# ARE_entrenadora_modular_Arduino_mod.net
KiCad netlist of a schematic drawn in EAGLE
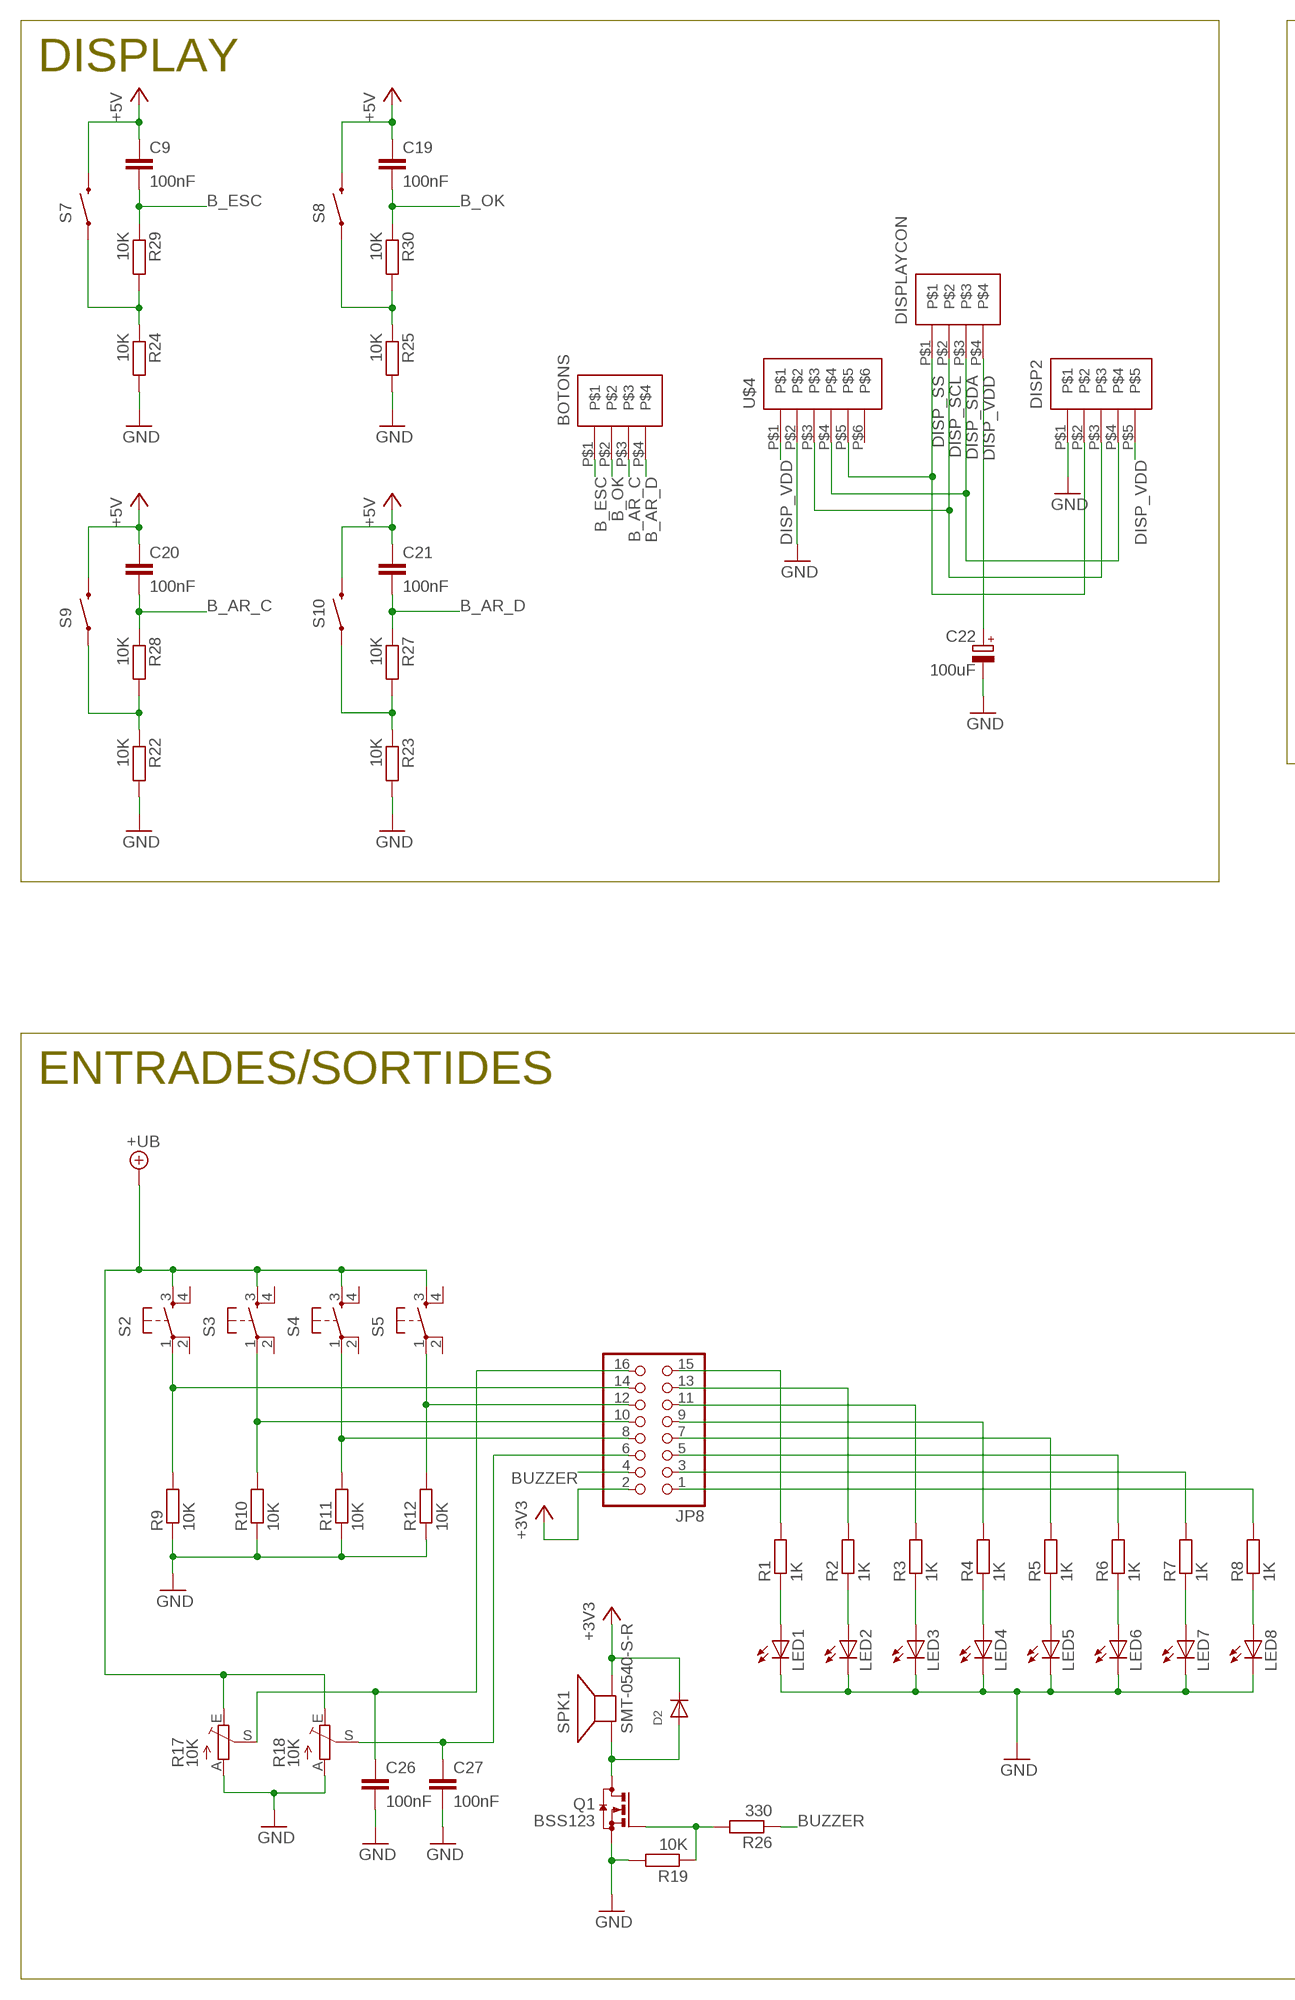
[diagram p0: schematic, sheet 1, part 1 of 2]
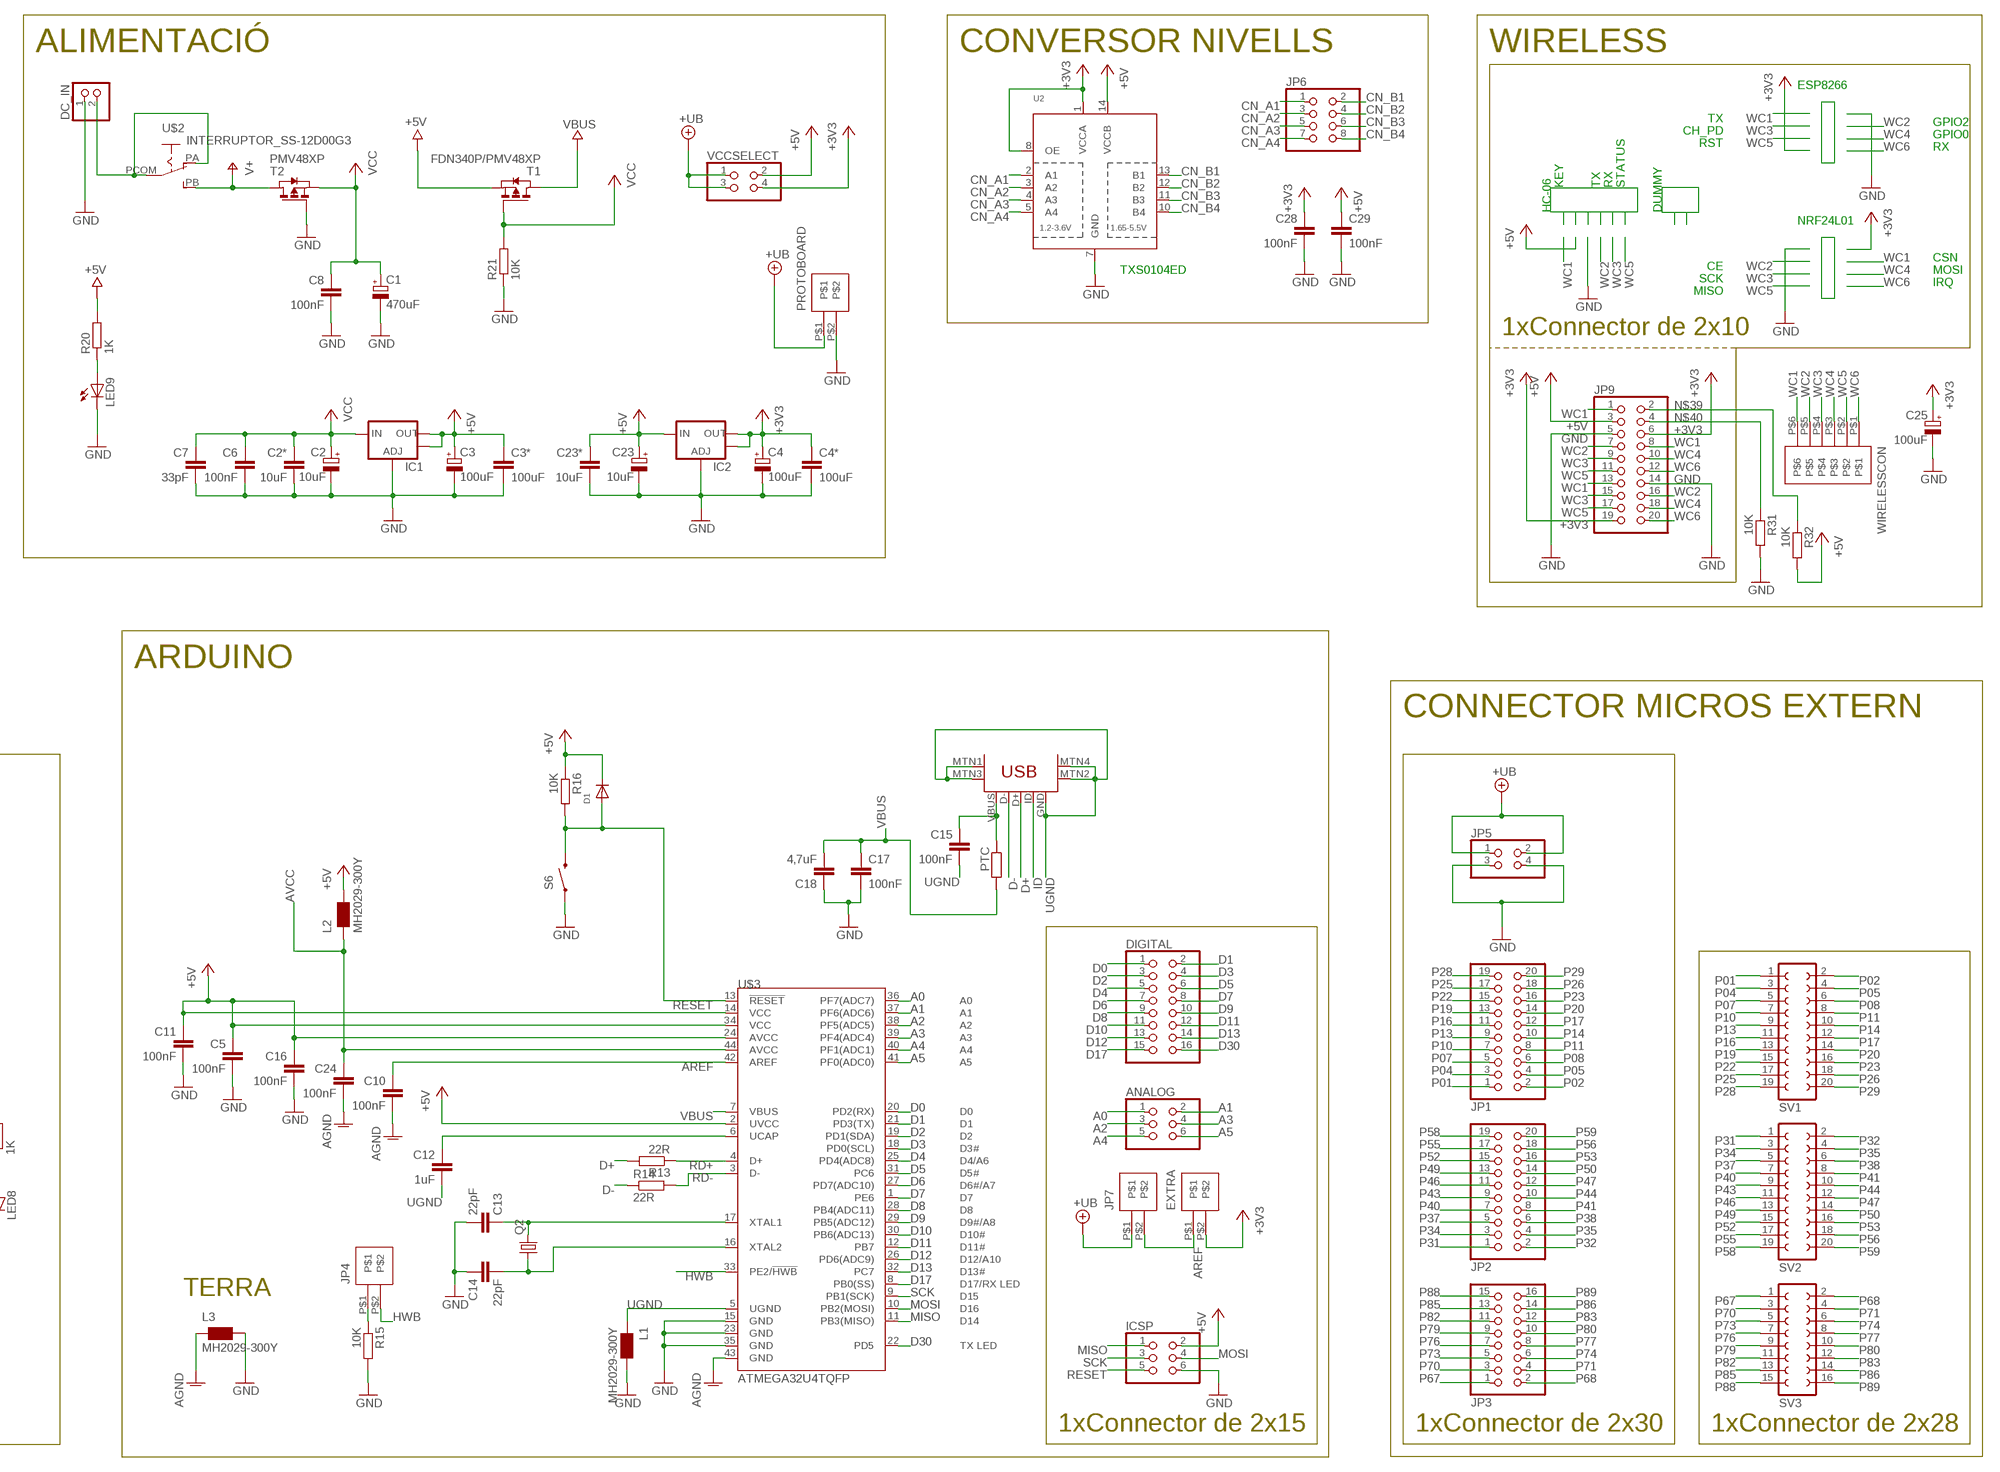
[diagram p1: schematic, sheet 1, part 2 of 2]

(export (version "E")
  (design (tool "Eeschema 10.0.6"))
  (components
    (comp (ref "ANALOG")
      (value "PINHD-2X3")
      (footprint "eagle-import:2X03")
      (libsource (lib "eagle-import") (part "PINHD-2X3"))
    )
    (comp (ref "BOTONS")
      (value "PINHEAD_1X4")
      (footprint "eagle-import:PINHEAD_1X4_2.54")
      (libsource (lib "eagle-import") (part "PINHEAD_1X4"))
    )
    (comp (ref "C1")
      (value "470uF")
      (footprint "eagle-import:E3,5-8")
      (libsource (lib "eagle-import") (part "CPOL-EUE3.5-8"))
    )
    (comp (ref "C2")
      (value "10uF")
      (footprint "eagle-import:SMC_C")
      (libsource (lib "eagle-import") (part "CPOL-EUSMCC"))
    )
    (comp (ref "C2*")
      (value "10uF")
      (footprint "eagle-import:C1206")
      (libsource (lib "eagle-import") (part "C-EUC1206"))
    )
    (comp (ref "C3")
      (value "100uF")
      (footprint "eagle-import:CT7343")
      (libsource (lib "eagle-import") (part "CPOL-EUCT7343"))
    )
    (comp (ref "C3*")
      (value "100uF")
      (footprint "eagle-import:C1206")
      (libsource (lib "eagle-import") (part "C-EUC1206"))
    )
    (comp (ref "C4")
      (value "100uF")
      (footprint "eagle-import:CT7343")
      (libsource (lib "eagle-import") (part "CPOL-EUCT7343"))
    )
    (comp (ref "C4*")
      (value "100uF")
      (footprint "eagle-import:C1206")
      (libsource (lib "eagle-import") (part "C-EUC1206"))
    )
    (comp (ref "C5")
      (value "100nF")
      (footprint "eagle-import:C0805")
      (libsource (lib "eagle-import") (part "C-EUC0805"))
    )
    (comp (ref "C6")
      (value "100nF")
      (footprint "eagle-import:C0805")
      (libsource (lib "eagle-import") (part "C-EUC0805"))
    )
    (comp (ref "C7")
      (value "33pF")
      (footprint "eagle-import:C0805")
      (libsource (lib "eagle-import") (part "C-EUC0805"))
    )
    (comp (ref "C8")
      (value "100nF")
      (footprint "eagle-import:C0805")
      (libsource (lib "eagle-import") (part "C-EUC0805"))
    )
    (comp (ref "C9")
      (value "100nF")
      (footprint "eagle-import:C0805")
      (libsource (lib "eagle-import") (part "C-EUC0805"))
    )
    (comp (ref "C10")
      (value "100nF")
      (footprint "eagle-import:C0805")
      (libsource (lib "eagle-import") (part "C-EUC0805"))
    )
    (comp (ref "C11")
      (value "100nF")
      (footprint "eagle-import:C0805")
      (libsource (lib "eagle-import") (part "C-EUC0805"))
    )
    (comp (ref "C12")
      (value "1uF")
      (footprint "eagle-import:C0805")
      (libsource (lib "eagle-import") (part "C-EUC0805"))
    )
    (comp (ref "C13")
      (value "22pF")
      (footprint "eagle-import:C0805")
      (libsource (lib "eagle-import") (part "C-EUC0805"))
    )
    (comp (ref "C14")
      (value "22pF")
      (footprint "eagle-import:C0805")
      (libsource (lib "eagle-import") (part "C-EUC0805"))
    )
    (comp (ref "C15")
      (value "100nF")
      (footprint "eagle-import:C0805")
      (libsource (lib "eagle-import") (part "C-EUC0805"))
    )
    (comp (ref "C16")
      (value "100nF")
      (footprint "eagle-import:C0805")
      (libsource (lib "eagle-import") (part "C-EUC0805"))
    )
    (comp (ref "C17")
      (value "100nF")
      (footprint "eagle-import:C0805")
      (libsource (lib "eagle-import") (part "C-EUC0805"))
    )
    (comp (ref "C18")
      (value "4,7uF")
      (footprint "eagle-import:C0805")
      (libsource (lib "eagle-import") (part "C-EUC0805"))
    )
    (comp (ref "C19")
      (value "100nF")
      (footprint "eagle-import:C0805")
      (libsource (lib "eagle-import") (part "C-EUC0805"))
    )
    (comp (ref "C20")
      (value "100nF")
      (footprint "eagle-import:C0805")
      (libsource (lib "eagle-import") (part "C-EUC0805"))
    )
    (comp (ref "C21")
      (value "100nF")
      (footprint "eagle-import:C0805")
      (libsource (lib "eagle-import") (part "C-EUC0805"))
    )
    (comp (ref "C22")
      (value "100uF")
      (footprint "eagle-import:SMC_C")
      (libsource (lib "eagle-import") (part "CPOL-EUSMCC"))
    )
    (comp (ref "C23")
      (value "10uF")
      (footprint "eagle-import:SMC_C")
      (libsource (lib "eagle-import") (part "CPOL-EUSMCC"))
    )
    (comp (ref "C23*")
      (value "10uF")
      (footprint "eagle-import:C1206")
      (libsource (lib "eagle-import") (part "C-EUC1206"))
    )
    (comp (ref "C24")
      (value "100nF")
      (footprint "eagle-import:C0805")
      (libsource (lib "eagle-import") (part "C-EUC0805"))
    )
    (comp (ref "C25")
      (value "100uF")
      (footprint "eagle-import:SMC_C")
      (libsource (lib "eagle-import") (part "CPOL-EUSMCC"))
    )
    (comp (ref "C26")
      (value "100nF")
      (footprint "eagle-import:C0805")
      (libsource (lib "eagle-import") (part "C-EUC0805"))
    )
    (comp (ref "C27")
      (value "100nF")
      (footprint "eagle-import:C0805")
      (libsource (lib "eagle-import") (part "C-EUC0805"))
    )
    (comp (ref "C28")
      (value "100nF")
      (footprint "eagle-import:C0805")
      (libsource (lib "eagle-import") (part "C-EUC0805"))
    )
    (comp (ref "C29")
      (value "100nF")
      (footprint "eagle-import:C0805")
      (libsource (lib "eagle-import") (part "C-EUC0805"))
    )
    (comp (ref "D1")
      (value "DIODESOD-123")
      (footprint "eagle-import:SOD-123")
      (libsource (lib "eagle-import") (part "DIODESOD-123"))
    )
    (comp (ref "D2")
      (value "DIODESOD-123")
      (footprint "eagle-import:SOD-123")
      (libsource (lib "eagle-import") (part "DIODESOD-123"))
    )
    (comp (ref "DC_IN")
      (value "PINHD-1X2/90")
      (footprint "eagle-import:1X02_90")
      (libsource (lib "eagle-import") (part "PINHD-1X2/90"))
    )
    (comp (ref "DIGITAL")
      (value "PINHD-2X8")
      (footprint "eagle-import:2X08")
      (libsource (lib "eagle-import") (part "PINHD-2X8"))
    )
    (comp (ref "DISP2")
      (value "PINHEAD_1X5")
      (footprint "eagle-import:PINHEAD_1X5_2.54")
      (libsource (lib "eagle-import") (part "PINHEAD_1X5"))
    )
    (comp (ref "DISPLAYCON")
      (value "PINHEAD_1X4")
      (footprint "eagle-import:PINHEAD_1X4_2.54")
      (libsource (lib "eagle-import") (part "PINHEAD_1X4"))
    )
    (comp (ref "EXTRA")
      (value "PINHEAD_1X2")
      (footprint "eagle-import:PINHEAD_1X2_2.54")
      (libsource (lib "eagle-import") (part "PINHEAD_1X2"))
    )
    (comp (ref "IC1")
      (value "V_REG_LM1117SOT223")
      (footprint "eagle-import:SOT223")
      (libsource (lib "eagle-import") (part "V_REG_LM1117SOT223"))
    )
    (comp (ref "IC2")
      (value "V_REG_LM1117SOT223")
      (footprint "eagle-import:SOT223")
      (libsource (lib "eagle-import") (part "V_REG_LM1117SOT223"))
    )
    (comp (ref "ICSP")
      (value "PINHD-2X3")
      (footprint "eagle-import:2X03")
      (libsource (lib "eagle-import") (part "PINHD-2X3"))
    )
    (comp (ref "JP1")
      (value "PINHD-2X10/90")
      (footprint "eagle-import:2X10_90")
      (libsource (lib "eagle-import") (part "PINHD-2X10/90"))
    )
    (comp (ref "JP2")
      (value "PINHD-2X10/90")
      (footprint "eagle-import:2X10_90")
      (libsource (lib "eagle-import") (part "PINHD-2X10/90"))
    )
    (comp (ref "JP3")
      (value "PINHD-2X8/90")
      (footprint "eagle-import:2X08_90")
      (libsource (lib "eagle-import") (part "PINHD-2X8/90"))
    )
    (comp (ref "JP4")
      (value "PINHEAD_1X2")
      (footprint "eagle-import:PINHEAD_1X2_2.54")
      (libsource (lib "eagle-import") (part "PINHEAD_1X2"))
    )
    (comp (ref "JP5")
      (value "PINHD-2X2/90")
      (footprint "eagle-import:2X02_90")
      (libsource (lib "eagle-import") (part "PINHD-2X2/90"))
    )
    (comp (ref "JP6")
      (value "PINHD-2X4")
      (footprint "eagle-import:2X04")
      (libsource (lib "eagle-import") (part "PINHD-2X4"))
    )
    (comp (ref "JP7")
      (value "PINHEAD_1X2")
      (footprint "eagle-import:PINHEAD_1X2_2.54")
      (libsource (lib "eagle-import") (part "PINHEAD_1X2"))
    )
    (comp (ref "JP8")
      (value "PINHD-2X8")
      (footprint "eagle-import:2X08")
      (libsource (lib "eagle-import") (part "PINHD-2X8"))
    )
    (comp (ref "JP9")
      (value "PINHD-2X10")
      (footprint "eagle-import:2X10")
      (libsource (lib "eagle-import") (part "PINHD-2X10"))
    )
    (comp (ref "L1")
      (value "MH2029-300Y")
      (footprint "eagle-import:0805")
      (libsource (lib "eagle-import") (part "WE-CBF_0805"))
    )
    (comp (ref "L2")
      (value "MH2029-300Y")
      (footprint "eagle-import:0805")
      (libsource (lib "eagle-import") (part "WE-CBF_0805"))
    )
    (comp (ref "L3")
      (value "MH2029-300Y")
      (footprint "eagle-import:0805")
      (libsource (lib "eagle-import") (part "WE-CBF_0805"))
    )
    (comp (ref "LED1")
      (value "LEDCHIP-LED0805")
      (footprint "eagle-import:CHIP-LED0805")
      (libsource (lib "eagle-import") (part "LEDCHIP-LED0805"))
    )
    (comp (ref "LED2")
      (value "LEDCHIP-LED0805")
      (footprint "eagle-import:CHIP-LED0805")
      (libsource (lib "eagle-import") (part "LEDCHIP-LED0805"))
    )
    (comp (ref "LED3")
      (value "LEDCHIP-LED0805")
      (footprint "eagle-import:CHIP-LED0805")
      (libsource (lib "eagle-import") (part "LEDCHIP-LED0805"))
    )
    (comp (ref "LED4")
      (value "LEDCHIP-LED0805")
      (footprint "eagle-import:CHIP-LED0805")
      (libsource (lib "eagle-import") (part "LEDCHIP-LED0805"))
    )
    (comp (ref "LED5")
      (value "LEDCHIP-LED0805")
      (footprint "eagle-import:CHIP-LED0805")
      (libsource (lib "eagle-import") (part "LEDCHIP-LED0805"))
    )
    (comp (ref "LED6")
      (value "LEDCHIP-LED0805")
      (footprint "eagle-import:CHIP-LED0805")
      (libsource (lib "eagle-import") (part "LEDCHIP-LED0805"))
    )
    (comp (ref "LED7")
      (value "LEDCHIP-LED0805")
      (footprint "eagle-import:CHIP-LED0805")
      (libsource (lib "eagle-import") (part "LEDCHIP-LED0805"))
    )
    (comp (ref "LED8")
      (value "LEDCHIP-LED0805")
      (footprint "eagle-import:CHIP-LED0805")
      (libsource (lib "eagle-import") (part "LEDCHIP-LED0805"))
    )
    (comp (ref "LED9")
      (value "LEDCHIP-LED0805")
      (footprint "eagle-import:CHIP-LED0805")
      (libsource (lib "eagle-import") (part "LEDCHIP-LED0805"))
    )
    (comp (ref "PROTOBOARD")
      (value "PINHEAD_1X2")
      (footprint "eagle-import:PINHEAD_1X2_2.54")
      (libsource (lib "eagle-import") (part "PINHEAD_1X2"))
    )
    (comp (ref "PTC")
      (value "R-EU_R1206")
      (footprint "eagle-import:R1206")
      (libsource (lib "eagle-import") (part "R-EU_R1206"))
    )
    (comp (ref "Q1")
      (value "BSS123")
      (footprint "eagle-import:SOT23")
      (libsource (lib "eagle-import") (part "BSS123"))
    )
    (comp (ref "Q2")
      (value "CRYSTALHC49UP")
      (footprint "eagle-import:HC49UP")
      (libsource (lib "eagle-import") (part "CRYSTALHC49UP"))
    )
    (comp (ref "R1")
      (value "1K")
      (footprint "eagle-import:R0805")
      (libsource (lib "eagle-import") (part "R-EU_R0805"))
    )
    (comp (ref "R2")
      (value "1K")
      (footprint "eagle-import:R0805")
      (libsource (lib "eagle-import") (part "R-EU_R0805"))
    )
    (comp (ref "R3")
      (value "1K")
      (footprint "eagle-import:R0805")
      (libsource (lib "eagle-import") (part "R-EU_R0805"))
    )
    (comp (ref "R4")
      (value "1K")
      (footprint "eagle-import:R0805")
      (libsource (lib "eagle-import") (part "R-EU_R0805"))
    )
    (comp (ref "R5")
      (value "1K")
      (footprint "eagle-import:R0805")
      (libsource (lib "eagle-import") (part "R-EU_R0805"))
    )
    (comp (ref "R6")
      (value "1K")
      (footprint "eagle-import:R0805")
      (libsource (lib "eagle-import") (part "R-EU_R0805"))
    )
    (comp (ref "R7")
      (value "1K")
      (footprint "eagle-import:R0805")
      (libsource (lib "eagle-import") (part "R-EU_R0805"))
    )
    (comp (ref "R8")
      (value "1K")
      (footprint "eagle-import:R0805")
      (libsource (lib "eagle-import") (part "R-EU_R0805"))
    )
    (comp (ref "R9")
      (value "10K")
      (footprint "eagle-import:R0805")
      (libsource (lib "eagle-import") (part "R-EU_R0805"))
    )
    (comp (ref "R10")
      (value "10K")
      (footprint "eagle-import:R0805")
      (libsource (lib "eagle-import") (part "R-EU_R0805"))
    )
    (comp (ref "R11")
      (value "10K")
      (footprint "eagle-import:R0805")
      (libsource (lib "eagle-import") (part "R-EU_R0805"))
    )
    (comp (ref "R12")
      (value "10K")
      (footprint "eagle-import:R0805")
      (libsource (lib "eagle-import") (part "R-EU_R0805"))
    )
    (comp (ref "R13")
      (value "22R")
      (footprint "eagle-import:R0805")
      (libsource (lib "eagle-import") (part "R-EU_R0805"))
    )
    (comp (ref "R14")
      (value "22R")
      (footprint "eagle-import:R0805")
      (libsource (lib "eagle-import") (part "R-EU_R0805"))
    )
    (comp (ref "R15")
      (value "10K")
      (footprint "eagle-import:R0805")
      (libsource (lib "eagle-import") (part "R-EU_R0805"))
    )
    (comp (ref "R16")
      (value "10K")
      (footprint "eagle-import:R0805")
      (libsource (lib "eagle-import") (part "R-EU_R0805"))
    )
    (comp (ref "R17")
      (value "10K")
      (footprint "eagle-import:CA6V")
      (libsource (lib "eagle-import") (part "TRIM_EU-CA6V"))
    )
    (comp (ref "R18")
      (value "10K")
      (footprint "eagle-import:CA6V")
      (libsource (lib "eagle-import") (part "TRIM_EU-CA6V"))
    )
    (comp (ref "R19")
      (value "10K")
      (footprint "eagle-import:R0805")
      (libsource (lib "eagle-import") (part "R-EU_R0805"))
    )
    (comp (ref "R20")
      (value "1K")
      (footprint "eagle-import:R0805")
      (libsource (lib "eagle-import") (part "R-EU_R0805"))
    )
    (comp (ref "R21")
      (value "10K")
      (footprint "eagle-import:R0805")
      (libsource (lib "eagle-import") (part "R-EU_R0805"))
    )
    (comp (ref "R22")
      (value "10K")
      (footprint "eagle-import:R0805")
      (libsource (lib "eagle-import") (part "R-EU_R0805"))
    )
    (comp (ref "R23")
      (value "10K")
      (footprint "eagle-import:R0805")
      (libsource (lib "eagle-import") (part "R-EU_R0805"))
    )
    (comp (ref "R24")
      (value "10K")
      (footprint "eagle-import:R0805")
      (libsource (lib "eagle-import") (part "R-EU_R0805"))
    )
    (comp (ref "R25")
      (value "10K")
      (footprint "eagle-import:R0805")
      (libsource (lib "eagle-import") (part "R-EU_R0805"))
    )
    (comp (ref "R26")
      (value "330")
      (footprint "eagle-import:R0805")
      (libsource (lib "eagle-import") (part "R-EU_R0805"))
    )
    (comp (ref "R27")
      (value "10K")
      (footprint "eagle-import:R0805")
      (libsource (lib "eagle-import") (part "R-EU_R0805"))
    )
    (comp (ref "R28")
      (value "10K")
      (footprint "eagle-import:R0805")
      (libsource (lib "eagle-import") (part "R-EU_R0805"))
    )
    (comp (ref "R29")
      (value "10K")
      (footprint "eagle-import:R0805")
      (libsource (lib "eagle-import") (part "R-EU_R0805"))
    )
    (comp (ref "R30")
      (value "10K")
      (footprint "eagle-import:R0805")
      (libsource (lib "eagle-import") (part "R-EU_R0805"))
    )
    (comp (ref "R31")
      (value "10K")
      (footprint "eagle-import:R0805")
      (libsource (lib "eagle-import") (part "R-EU_R0805"))
    )
    (comp (ref "R32")
      (value "10K")
      (footprint "eagle-import:R0805")
      (libsource (lib "eagle-import") (part "R-EU_R0805"))
    )
    (comp (ref "S2")
      (value "TAC_SWITCHPTH")
      (footprint "eagle-import:TACTILE-PTH")
      (libsource (lib "eagle-import") (part "TAC_SWITCHPTH"))
    )
    (comp (ref "S3")
      (value "TAC_SWITCHPTH")
      (footprint "eagle-import:TACTILE-PTH")
      (libsource (lib "eagle-import") (part "TAC_SWITCHPTH"))
    )
    (comp (ref "S4")
      (value "TAC_SWITCHPTH")
      (footprint "eagle-import:TACTILE-PTH")
      (libsource (lib "eagle-import") (part "TAC_SWITCHPTH"))
    )
    (comp (ref "S5")
      (value "TAC_SWITCHPTH")
      (footprint "eagle-import:TACTILE-PTH")
      (libsource (lib "eagle-import") (part "TAC_SWITCHPTH"))
    )
    (comp (ref "S6")
      (value "SWITCH-MOMENTARY-2-SMD-1101NE")
      (footprint "eagle-import:TACTILE-SWITCH-1101NE")
      (libsource (lib "eagle-import") (part "SWITCH-MOMENTARY-2-SMD-1101NE"))
    )
    (comp (ref "S7")
      (value "SWITCH-MOMENTARY-2-SMD-1101NE")
      (footprint "eagle-import:TACTILE-SWITCH-1101NE")
      (libsource (lib "eagle-import") (part "SWITCH-MOMENTARY-2-SMD-1101NE"))
    )
    (comp (ref "S8")
      (value "SWITCH-MOMENTARY-2-SMD-1101NE")
      (footprint "eagle-import:TACTILE-SWITCH-1101NE")
      (libsource (lib "eagle-import") (part "SWITCH-MOMENTARY-2-SMD-1101NE"))
    )
    (comp (ref "S9")
      (value "SWITCH-MOMENTARY-2-SMD-1101NE")
      (footprint "eagle-import:TACTILE-SWITCH-1101NE")
      (libsource (lib "eagle-import") (part "SWITCH-MOMENTARY-2-SMD-1101NE"))
    )
    (comp (ref "S10")
      (value "SWITCH-MOMENTARY-2-SMD-1101NE")
      (footprint "eagle-import:TACTILE-SWITCH-1101NE")
      (libsource (lib "eagle-import") (part "SWITCH-MOMENTARY-2-SMD-1101NE"))
    )
    (comp (ref "SPK1")
      (value "SMT-0540-S-R")
      (footprint "eagle-import:SMT-0540-S-R")
      (libsource (lib "eagle-import") (part "SMT-0540-S-R"))
    )
    (comp (ref "SV1")
      (value "FE10-2")
      (footprint "eagle-import:FE10-2")
      (libsource (lib "eagle-import") (part "FE10-2"))
    )
    (comp (ref "SV2")
      (value "FE10-2")
      (footprint "eagle-import:FE10-2")
      (fields (field (name "OC_FARNELL") "unknown") (field (name "OC_NEWARK") "unknown"))
      (libsource (lib "eagle-import") (part "FE10-2"))
    )
    (comp (ref "SV3")
      (value "FE08-2")
      (footprint "eagle-import:FE08-2")
      (libsource (lib "eagle-import") (part "FE08-2"))
    )
    (comp (ref "T1")
      (value "FDN340P/PMV48XP")
      (footprint "eagle-import:SOT-23")
      (libsource (lib "eagle-import") (part "PMOSSOT23"))
    )
    (comp (ref "T2")
      (value "PMV48XP")
      (footprint "eagle-import:SOT-23")
      (libsource (lib "eagle-import") (part "PMOSSOT23"))
    )
    (comp (ref "U$1")
      (value "USB-MINIB-5PIN")
      (footprint "eagle-import:USB-MINIB")
      (libsource (lib "eagle-import") (part "USB-MINIB-5PIN"))
    )
    (comp (ref "U$2")
      (value "INTERRUPTOR_SS-12D00G3")
      (footprint "eagle-import:SS-12D00G3")
      (libsource (lib "eagle-import") (part "INTERRUPTOR_SS-12D00G3"))
    )
    (comp (ref "U$3")
      (value "ATMEGA32U4TQFP")
      (footprint "eagle-import:SPARKFUN-DIGITALIC_TQFP44")
      (libsource (lib "eagle-import") (part "ATMEGA32U4TQFP"))
    )
    (comp (ref "U$4")
      (value "PINHEAD_1X6")
      (footprint "eagle-import:PINHEAD_1X6_2.54")
      (libsource (lib "eagle-import") (part "PINHEAD_1X6"))
    )
    (comp (ref "U2")
      (value "TXB0104PWRSOIC14")
      (footprint "eagle-import:SO14")
      (libsource (lib "eagle-import") (part "TXB0104PWRSOIC14"))
    )
    (comp (ref "VCCSELECT")
      (value "PINHD-2X2")
      (footprint "eagle-import:2X02")
      (libsource (lib "eagle-import") (part "PINHD-2X2"))
    )
    (comp (ref "WIRELESSCON")
      (value "PINHEAD_1X6")
      (footprint "eagle-import:PINHEAD_1X6_2.54")
      (libsource (lib "eagle-import") (part "PINHEAD_1X6"))
    )
  )
  (nets
    (net (code "1") (name "+3V3") (class "Default")
      (node (ref "C25") (pin "+") (pinfunction "+_+") (pintype "passive"))
      (node (ref "C28") (pin "1") (pinfunction "1_1") (pintype "passive"))
      (node (ref "C4") (pin "+") (pinfunction "+_+") (pintype "passive"))
      (node (ref "C4*") (pin "1") (pinfunction "1_1") (pintype "passive"))
      (node (ref "D2") (pin "C") (pinfunction "C_C") (pintype "passive"))
      (node (ref "EXTRA") (pin "P$2") (pinfunction "P$2_P$2") (pintype "bidirectional"))
      (node (ref "IC2") (pin "2") (pinfunction "OUT_2") (pintype "output"))
      (node (ref "IC2") (pin "4") (pinfunction "OUT_4") (pintype "output"))
      (node (ref "JP8") (pin "2") (pinfunction "2_2") (pintype "passive"))
      (node (ref "JP9") (pin "19") (pinfunction "19_19") (pintype "passive"))
      (node (ref "JP9") (pin "6") (pinfunction "6_6") (pintype "passive"))
      (node (ref "SPK1") (pin "+") (pinfunction "-_+") (pintype "passive"))
      (node (ref "U2") (pin "1") (pinfunction "VCCA_1") (pintype "bidirectional"))
      (node (ref "U2") (pin "8") (pinfunction "OE_8") (pintype "bidirectional"))
      (node (ref "VCCSELECT") (pin "4") (pinfunction "4_4") (pintype "passive"))
    )
    (net (code "2") (name "+5V") (class "Default")
      (node (ref "C11") (pin "1") (pinfunction "1_1") (pintype "passive"))
      (node (ref "C16") (pin "1") (pinfunction "1_1") (pintype "passive"))
      (node (ref "C19") (pin "1") (pinfunction "1_1") (pintype "passive"))
      (node (ref "C20") (pin "1") (pinfunction "1_1") (pintype "passive"))
      (node (ref "C21") (pin "1") (pinfunction "1_1") (pintype "passive"))
      (node (ref "C23") (pin "+") (pinfunction "+_+") (pintype "passive"))
      (node (ref "C23*") (pin "1") (pinfunction "1_1") (pintype "passive"))
      (node (ref "C29") (pin "1") (pinfunction "1_1") (pintype "passive"))
      (node (ref "C3") (pin "+") (pinfunction "+_+") (pintype "passive"))
      (node (ref "C3*") (pin "1") (pinfunction "1_1") (pintype "passive"))
      (node (ref "C5") (pin "1") (pinfunction "1_1") (pintype "passive"))
      (node (ref "C9") (pin "1") (pinfunction "1_1") (pintype "passive"))
      (node (ref "D1") (pin "C") (pinfunction "C_C") (pintype "passive"))
      (node (ref "IC1") (pin "2") (pinfunction "OUT_2") (pintype "output"))
      (node (ref "IC1") (pin "4") (pinfunction "OUT_4") (pintype "output"))
      (node (ref "IC2") (pin "3") (pinfunction "IN_3") (pintype "input"))
      (node (ref "ICSP") (pin "2") (pinfunction "2_2") (pintype "passive"))
      (node (ref "JP9") (pin "3") (pinfunction "3_3") (pintype "passive"))
      (node (ref "L2") (pin "2") (pinfunction "2_2") (pintype "passive"))
      (node (ref "R16") (pin "1") (pinfunction "1_1") (pintype "passive"))
      (node (ref "R20") (pin "2") (pinfunction "2_2") (pintype "passive"))
      (node (ref "R32") (pin "2") (pinfunction "2_2") (pintype "passive"))
      (node (ref "S10") (pin "P$2") (pinfunction "2_P$2") (pintype "passive"))
      (node (ref "S7") (pin "P$2") (pinfunction "2_P$2") (pintype "passive"))
      (node (ref "S8") (pin "P$2") (pinfunction "2_P$2") (pintype "passive"))
      (node (ref "S9") (pin "P$2") (pinfunction "2_P$2") (pintype "passive"))
      (node (ref "T1") (pin "2") (pinfunction "S_2") (pintype "passive"))
      (node (ref "U$3") (pin "14") (pinfunction "VCC_14") (pintype "bidirectional"))
      (node (ref "U$3") (pin "2") (pinfunction "UVCC_2") (pintype "bidirectional"))
      (node (ref "U$3") (pin "24") (pinfunction "AVCC_24") (pintype "bidirectional"))
      (node (ref "U$3") (pin "34") (pinfunction "VCC_34") (pintype "bidirectional"))
      (node (ref "U2") (pin "14") (pinfunction "VCCB_14") (pintype "bidirectional"))
      (node (ref "VCCSELECT") (pin "2") (pinfunction "2_2") (pintype "passive"))
    )
    (net (code "3") (name "+UB") (class "Default")
      (node (ref "JP5") (pin "1") (pinfunction "1_1") (pintype "passive"))
      (node (ref "JP5") (pin "2") (pinfunction "2_2") (pintype "passive"))
      (node (ref "JP7") (pin "P$1") (pinfunction "P$1_P$1") (pintype "bidirectional"))
      (node (ref "PROTOBOARD") (pin "P$1") (pinfunction "P$1_P$1") (pintype "bidirectional"))
      (node (ref "R17") (pin "E") (pinfunction "E_E") (pintype "passive"))
      (node (ref "R18") (pin "E") (pinfunction "E_E") (pintype "passive"))
      (node (ref "S2") (pin "3") (pinfunction "3_3") (pintype "passive"))
      (node (ref "S3") (pin "3") (pinfunction "3_3") (pintype "passive"))
      (node (ref "S4") (pin "3") (pinfunction "3_3") (pintype "passive"))
      (node (ref "S5") (pin "3") (pinfunction "3_3") (pintype "passive"))
      (node (ref "VCCSELECT") (pin "1") (pinfunction "1_1") (pintype "passive"))
      (node (ref "VCCSELECT") (pin "3") (pinfunction "3_3") (pintype "passive"))
    )
    (net (code "4") (name "/A0") (class "Default")
      (node (ref "ANALOG") (pin "1") (pinfunction "1_1") (pintype "passive"))
      (node (ref "U$3") (pin "36") (pinfunction "PF7(ADC7)_36") (pintype "bidirectional"))
    )
    (net (code "5") (name "/A1") (class "Default")
      (node (ref "ANALOG") (pin "2") (pinfunction "2_2") (pintype "passive"))
      (node (ref "U$3") (pin "37") (pinfunction "PF6(ADC6)_37") (pintype "bidirectional"))
    )
    (net (code "6") (name "/A2") (class "Default")
      (node (ref "ANALOG") (pin "3") (pinfunction "3_3") (pintype "passive"))
      (node (ref "U$3") (pin "38") (pinfunction "PF5(ADC5)_38") (pintype "bidirectional"))
    )
    (net (code "7") (name "/A3") (class "Default")
      (node (ref "ANALOG") (pin "4") (pinfunction "4_4") (pintype "passive"))
      (node (ref "U$3") (pin "39") (pinfunction "PF4(ADC4)_39") (pintype "bidirectional"))
    )
    (net (code "8") (name "/A4") (class "Default")
      (node (ref "ANALOG") (pin "5") (pinfunction "5_5") (pintype "passive"))
      (node (ref "U$3") (pin "40") (pinfunction "PF1(ADC1)_40") (pintype "bidirectional"))
    )
    (net (code "9") (name "/A5") (class "Default")
      (node (ref "ANALOG") (pin "6") (pinfunction "6_6") (pintype "passive"))
      (node (ref "U$3") (pin "41") (pinfunction "PF0(ADC0)_41") (pintype "bidirectional"))
    )
    (net (code "10") (name "/AREF") (class "Default")
      (node (ref "C10") (pin "1") (pinfunction "1_1") (pintype "passive"))
      (node (ref "EXTRA") (pin "P$1") (pinfunction "P$1_P$1") (pintype "bidirectional"))
      (node (ref "JP7") (pin "P$2") (pinfunction "P$2_P$2") (pintype "bidirectional"))
      (node (ref "U$3") (pin "42") (pinfunction "AREF_42") (pintype "bidirectional"))
    )
    (net (code "11") (name "/AVCC") (class "Default")
      (node (ref "C24") (pin "1") (pinfunction "1_1") (pintype "passive"))
      (node (ref "L2") (pin "1") (pinfunction "1_1") (pintype "passive"))
      (node (ref "U$3") (pin "44") (pinfunction "AVCC_44") (pintype "bidirectional"))
    )
    (net (code "12") (name "/BUZZER") (class "Default")
      (node (ref "JP8") (pin "4") (pinfunction "4_4") (pintype "passive"))
      (node (ref "R26") (pin "1") (pinfunction "1_1") (pintype "passive"))
    )
    (net (code "13") (name "/B_AR_C") (class "Default")
      (node (ref "BOTONS") (pin "P$3") (pinfunction "P$3_P$3") (pintype "bidirectional"))
      (node (ref "C20") (pin "2") (pinfunction "2_2") (pintype "passive"))
      (node (ref "R28") (pin "1") (pinfunction "1_1") (pintype "passive"))
    )
    (net (code "14") (name "/B_AR_D") (class "Default")
      (node (ref "BOTONS") (pin "P$4") (pinfunction "P$4_P$4") (pintype "bidirectional"))
      (node (ref "C21") (pin "2") (pinfunction "2_2") (pintype "passive"))
      (node (ref "R27") (pin "1") (pinfunction "1_1") (pintype "passive"))
    )
    (net (code "15") (name "/B_ESC") (class "Default")
      (node (ref "BOTONS") (pin "P$1") (pinfunction "P$1_P$1") (pintype "bidirectional"))
      (node (ref "C9") (pin "2") (pinfunction "2_2") (pintype "passive"))
      (node (ref "R29") (pin "1") (pinfunction "1_1") (pintype "passive"))
    )
    (net (code "16") (name "/B_OK") (class "Default")
      (node (ref "BOTONS") (pin "P$2") (pinfunction "P$2_P$2") (pintype "bidirectional"))
      (node (ref "C19") (pin "2") (pinfunction "2_2") (pintype "passive"))
      (node (ref "R30") (pin "1") (pinfunction "1_1") (pintype "passive"))
    )
    (net (code "17") (name "/CN_A1") (class "Default")
      (node (ref "JP6") (pin "1") (pinfunction "1_1") (pintype "passive"))
      (node (ref "U2") (pin "2") (pinfunction "A1_2") (pintype "bidirectional"))
    )
    (net (code "18") (name "/CN_A2") (class "Default")
      (node (ref "JP6") (pin "3") (pinfunction "3_3") (pintype "passive"))
      (node (ref "U2") (pin "3") (pinfunction "A2_3") (pintype "bidirectional"))
    )
    (net (code "19") (name "/CN_A3") (class "Default")
      (node (ref "JP6") (pin "5") (pinfunction "5_5") (pintype "passive"))
      (node (ref "U2") (pin "4") (pinfunction "A3_4") (pintype "bidirectional"))
    )
    (net (code "20") (name "/CN_A4") (class "Default")
      (node (ref "JP6") (pin "7") (pinfunction "7_7") (pintype "passive"))
      (node (ref "U2") (pin "5") (pinfunction "A4_5") (pintype "bidirectional"))
    )
    (net (code "21") (name "/CN_B1") (class "Default")
      (node (ref "JP6") (pin "2") (pinfunction "2_2") (pintype "passive"))
      (node (ref "U2") (pin "13") (pinfunction "B1_13") (pintype "bidirectional"))
    )
    (net (code "22") (name "/CN_B2") (class "Default")
      (node (ref "JP6") (pin "4") (pinfunction "4_4") (pintype "passive"))
      (node (ref "U2") (pin "12") (pinfunction "B2_12") (pintype "bidirectional"))
    )
    (net (code "23") (name "/CN_B3") (class "Default")
      (node (ref "JP6") (pin "6") (pinfunction "6_6") (pintype "passive"))
      (node (ref "U2") (pin "11") (pinfunction "B3_11") (pintype "bidirectional"))
    )
    (net (code "24") (name "/CN_B4") (class "Default")
      (node (ref "JP6") (pin "8") (pinfunction "8_8") (pintype "passive"))
      (node (ref "U2") (pin "10") (pinfunction "B4_10") (pintype "bidirectional"))
    )
    (net (code "25") (name "/D+") (class "Default")
      (node (ref "R13") (pin "2") (pinfunction "2_2") (pintype "passive"))
      (node (ref "U$1") (pin "D+") (pinfunction "D+_D+") (pintype "bidirectional"))
    )
    (net (code "26") (name "/D-") (class "Default")
      (node (ref "R14") (pin "1") (pinfunction "1_1") (pintype "passive"))
      (node (ref "U$1") (pin "D-") (pinfunction "D-_D-") (pintype "bidirectional"))
    )
    (net (code "27") (name "/D0") (class "Default")
      (node (ref "DIGITAL") (pin "1") (pinfunction "1_1") (pintype "passive"))
      (node (ref "U$3") (pin "20") (pinfunction "PD2(RX)_20") (pintype "bidirectional"))
    )
    (net (code "28") (name "/D1") (class "Default")
      (node (ref "DIGITAL") (pin "2") (pinfunction "2_2") (pintype "passive"))
      (node (ref "U$3") (pin "21") (pinfunction "PD3(TX)_21") (pintype "bidirectional"))
    )
    (net (code "29") (name "/D2") (class "Default")
      (node (ref "DIGITAL") (pin "3") (pinfunction "3_3") (pintype "passive"))
      (node (ref "U$3") (pin "19") (pinfunction "PD1(SDA)_19") (pintype "bidirectional"))
    )
    (net (code "30") (name "/D3") (class "Default")
      (node (ref "DIGITAL") (pin "4") (pinfunction "4_4") (pintype "passive"))
      (node (ref "U$3") (pin "18") (pinfunction "PD0(SCL)_18") (pintype "bidirectional"))
    )
    (net (code "31") (name "/D4") (class "Default")
      (node (ref "DIGITAL") (pin "5") (pinfunction "5_5") (pintype "passive"))
      (node (ref "U$3") (pin "25") (pinfunction "PD4(ADC8)_25") (pintype "bidirectional"))
    )
    (net (code "32") (name "/D5") (class "Default")
      (node (ref "DIGITAL") (pin "6") (pinfunction "6_6") (pintype "passive"))
      (node (ref "U$3") (pin "31") (pinfunction "PC6_31") (pintype "bidirectional"))
    )
    (net (code "33") (name "/D6") (class "Default")
      (node (ref "DIGITAL") (pin "7") (pinfunction "7_7") (pintype "passive"))
      (node (ref "U$3") (pin "27") (pinfunction "PD7(ADC10)_27") (pintype "bidirectional"))
    )
    (net (code "34") (name "/D7") (class "Default")
      (node (ref "DIGITAL") (pin "8") (pinfunction "8_8") (pintype "passive"))
      (node (ref "U$3") (pin "1") (pinfunction "PE6_1") (pintype "bidirectional"))
    )
    (net (code "35") (name "/D8") (class "Default")
      (node (ref "DIGITAL") (pin "9") (pinfunction "9_9") (pintype "passive"))
      (node (ref "U$3") (pin "28") (pinfunction "PB4(ADC11)_28") (pintype "bidirectional"))
    )
    (net (code "36") (name "/D9") (class "Default")
      (node (ref "DIGITAL") (pin "10") (pinfunction "10_10") (pintype "passive"))
      (node (ref "U$3") (pin "29") (pinfunction "PB5(ADC12)_29") (pintype "bidirectional"))
    )
    (net (code "37") (name "/D10") (class "Default")
      (node (ref "DIGITAL") (pin "11") (pinfunction "11_11") (pintype "passive"))
      (node (ref "U$3") (pin "30") (pinfunction "PB6(ADC13)_30") (pintype "bidirectional"))
    )
    (net (code "38") (name "/D11") (class "Default")
      (node (ref "DIGITAL") (pin "12") (pinfunction "12_12") (pintype "passive"))
      (node (ref "U$3") (pin "12") (pinfunction "PB7_12") (pintype "bidirectional"))
    )
    (net (code "39") (name "/D12") (class "Default")
      (node (ref "DIGITAL") (pin "13") (pinfunction "13_13") (pintype "passive"))
      (node (ref "U$3") (pin "26") (pinfunction "PD6(ADC9)_26") (pintype "bidirectional"))
    )
    (net (code "40") (name "/D13") (class "Default")
      (node (ref "DIGITAL") (pin "14") (pinfunction "14_14") (pintype "passive"))
      (node (ref "U$3") (pin "32") (pinfunction "PC7_32") (pintype "bidirectional"))
    )
    (net (code "41") (name "/D17") (class "Default")
      (node (ref "DIGITAL") (pin "15") (pinfunction "15_15") (pintype "passive"))
      (node (ref "U$3") (pin "8") (pinfunction "PB0(SS)_8") (pintype "bidirectional"))
    )
    (net (code "42") (name "/D30") (class "Default")
      (node (ref "DIGITAL") (pin "16") (pinfunction "16_16") (pintype "passive"))
      (node (ref "U$3") (pin "22") (pinfunction "PD5_22") (pintype "bidirectional"))
    )
    (net (code "43") (name "/DISP_SCL") (class "Default")
      (node (ref "DISP2") (pin "P$3") (pinfunction "P$3_P$3") (pintype "bidirectional"))
      (node (ref "DISPLAYCON") (pin "P$2") (pinfunction "P$2_P$2") (pintype "bidirectional"))
      (node (ref "U$4") (pin "P$3") (pinfunction "P$3_P$3") (pintype "bidirectional"))
    )
    (net (code "44") (name "/DISP_SDA") (class "Default")
      (node (ref "DISP2") (pin "P$4") (pinfunction "P$4_P$4") (pintype "bidirectional"))
      (node (ref "DISPLAYCON") (pin "P$3") (pinfunction "P$3_P$3") (pintype "bidirectional"))
      (node (ref "U$4") (pin "P$4") (pinfunction "P$4_P$4") (pintype "bidirectional"))
    )
    (net (code "45") (name "/DISP_SS") (class "Default")
      (node (ref "DISP2") (pin "P$2") (pinfunction "P$2_P$2") (pintype "bidirectional"))
      (node (ref "DISPLAYCON") (pin "P$1") (pinfunction "P$1_P$1") (pintype "bidirectional"))
      (node (ref "U$4") (pin "P$5") (pinfunction "P$5_P$5") (pintype "bidirectional"))
    )
    (net (code "46") (name "/DISP_VDD") (class "Default")
      (node (ref "C22") (pin "+") (pinfunction "+_+") (pintype "passive"))
      (node (ref "DISP2") (pin "P$5") (pinfunction "P$5_P$5") (pintype "bidirectional"))
      (node (ref "DISPLAYCON") (pin "P$4") (pinfunction "P$4_P$4") (pintype "bidirectional"))
      (node (ref "U$4") (pin "P$1") (pinfunction "P$1_P$1") (pintype "bidirectional"))
    )
    (net (code "47") (name "/HWB") (class "Default")
      (node (ref "JP4") (pin "P$2") (pinfunction "P$2_P$2") (pintype "bidirectional"))
      (node (ref "U$3") (pin "33") (pinfunction "PE2/~{HWB}_33") (pintype "bidirectional"))
    )
    (net (code "48") (name "/ID") (class "Default")
      (node (ref "U$1") (pin "ID") (pinfunction "ID_ID") (pintype "bidirectional"))
    )
    (net (code "49") (name "/MISO") (class "Default")
      (node (ref "ICSP") (pin "1") (pinfunction "1_1") (pintype "passive"))
      (node (ref "U$3") (pin "11") (pinfunction "PB3(MISO)_11") (pintype "bidirectional"))
    )
    (net (code "50") (name "/MOSI") (class "Default")
      (node (ref "ICSP") (pin "4") (pinfunction "4_4") (pintype "passive"))
      (node (ref "U$3") (pin "10") (pinfunction "PB2(MOSI)_10") (pintype "bidirectional"))
    )
    (net (code "51") (name "/N$39") (class "Default")
      (node (ref "JP9") (pin "2") (pinfunction "2_2") (pintype "passive"))
      (node (ref "R32") (pin "1") (pinfunction "1_1") (pintype "passive"))
    )
    (net (code "52") (name "/N$40") (class "Default")
      (node (ref "JP9") (pin "4") (pinfunction "4_4") (pintype "passive"))
      (node (ref "R31") (pin "1") (pinfunction "1_1") (pintype "passive"))
    )
    (net (code "53") (name "/P01") (class "Default")
      (node (ref "JP1") (pin "1") (pinfunction "1_1") (pintype "passive"))
      (node (ref "SV1") (pin "1") (pinfunction "1_1") (pintype "passive"))
    )
    (net (code "54") (name "/P02") (class "Default")
      (node (ref "JP1") (pin "2") (pinfunction "2_2") (pintype "passive"))
      (node (ref "SV1") (pin "2") (pinfunction "2_2") (pintype "passive"))
    )
    (net (code "55") (name "/P04") (class "Default")
      (node (ref "JP1") (pin "3") (pinfunction "3_3") (pintype "passive"))
      (node (ref "SV1") (pin "3") (pinfunction "3_3") (pintype "passive"))
    )
    (net (code "56") (name "/P05") (class "Default")
      (node (ref "JP1") (pin "4") (pinfunction "4_4") (pintype "passive"))
      (node (ref "SV1") (pin "4") (pinfunction "4_4") (pintype "passive"))
    )
    (net (code "57") (name "/P07") (class "Default")
      (node (ref "JP1") (pin "5") (pinfunction "5_5") (pintype "passive"))
      (node (ref "SV1") (pin "5") (pinfunction "5_5") (pintype "passive"))
    )
    (net (code "58") (name "/P08") (class "Default")
      (node (ref "JP1") (pin "6") (pinfunction "6_6") (pintype "passive"))
      (node (ref "SV1") (pin "6") (pinfunction "6_6") (pintype "passive"))
    )
    (net (code "59") (name "/P10") (class "Default")
      (node (ref "JP1") (pin "7") (pinfunction "7_7") (pintype "passive"))
      (node (ref "SV1") (pin "7") (pinfunction "7_7") (pintype "passive"))
    )
    (net (code "60") (name "/P11") (class "Default")
      (node (ref "JP1") (pin "8") (pinfunction "8_8") (pintype "passive"))
      (node (ref "SV1") (pin "8") (pinfunction "8_8") (pintype "passive"))
    )
    (net (code "61") (name "/P13") (class "Default")
      (node (ref "JP1") (pin "9") (pinfunction "9_9") (pintype "passive"))
      (node (ref "SV1") (pin "9") (pinfunction "9_9") (pintype "passive"))
    )
    (net (code "62") (name "/P14") (class "Default")
      (node (ref "JP1") (pin "10") (pinfunction "10_10") (pintype "passive"))
      (node (ref "SV1") (pin "10") (pinfunction "10_10") (pintype "passive"))
    )
    (net (code "63") (name "/P16") (class "Default")
      (node (ref "JP1") (pin "11") (pinfunction "11_11") (pintype "passive"))
      (node (ref "SV1") (pin "11") (pinfunction "11_11") (pintype "passive"))
    )
    (net (code "64") (name "/P17") (class "Default")
      (node (ref "JP1") (pin "12") (pinfunction "12_12") (pintype "passive"))
      (node (ref "SV1") (pin "12") (pinfunction "12_12") (pintype "passive"))
    )
    (net (code "65") (name "/P19") (class "Default")
      (node (ref "JP1") (pin "13") (pinfunction "13_13") (pintype "passive"))
      (node (ref "SV1") (pin "13") (pinfunction "13_13") (pintype "passive"))
    )
    (net (code "66") (name "/P20") (class "Default")
      (node (ref "JP1") (pin "14") (pinfunction "14_14") (pintype "passive"))
      (node (ref "SV1") (pin "14") (pinfunction "14_14") (pintype "passive"))
    )
    (net (code "67") (name "/P22") (class "Default")
      (node (ref "JP1") (pin "15") (pinfunction "15_15") (pintype "passive"))
      (node (ref "SV1") (pin "15") (pinfunction "15_15") (pintype "passive"))
    )
    (net (code "68") (name "/P23") (class "Default")
      (node (ref "JP1") (pin "16") (pinfunction "16_16") (pintype "passive"))
      (node (ref "SV1") (pin "16") (pinfunction "16_16") (pintype "passive"))
    )
    (net (code "69") (name "/P25") (class "Default")
      (node (ref "JP1") (pin "17") (pinfunction "17_17") (pintype "passive"))
      (node (ref "SV1") (pin "17") (pinfunction "17_17") (pintype "passive"))
    )
    (net (code "70") (name "/P26") (class "Default")
      (node (ref "JP1") (pin "18") (pinfunction "18_18") (pintype "passive"))
      (node (ref "SV1") (pin "18") (pinfunction "18_18") (pintype "passive"))
    )
    (net (code "71") (name "/P28") (class "Default")
      (node (ref "JP1") (pin "19") (pinfunction "19_19") (pintype "passive"))
      (node (ref "SV1") (pin "19") (pinfunction "19_19") (pintype "passive"))
    )
    (net (code "72") (name "/P29") (class "Default")
      (node (ref "JP1") (pin "20") (pinfunction "20_20") (pintype "passive"))
      (node (ref "SV1") (pin "20") (pinfunction "20_20") (pintype "passive"))
    )
    (net (code "73") (name "/P31") (class "Default")
      (node (ref "JP2") (pin "1") (pinfunction "1_1") (pintype "passive"))
      (node (ref "SV2") (pin "1") (pinfunction "1_1") (pintype "passive"))
    )
    (net (code "74") (name "/P32") (class "Default")
      (node (ref "JP2") (pin "2") (pinfunction "2_2") (pintype "passive"))
      (node (ref "SV2") (pin "2") (pinfunction "2_2") (pintype "passive"))
    )
    (net (code "75") (name "/P34") (class "Default")
      (node (ref "JP2") (pin "3") (pinfunction "3_3") (pintype "passive"))
      (node (ref "SV2") (pin "3") (pinfunction "3_3") (pintype "passive"))
    )
    (net (code "76") (name "/P35") (class "Default")
      (node (ref "JP2") (pin "4") (pinfunction "4_4") (pintype "passive"))
      (node (ref "SV2") (pin "4") (pinfunction "4_4") (pintype "passive"))
    )
    (net (code "77") (name "/P37") (class "Default")
      (node (ref "JP2") (pin "5") (pinfunction "5_5") (pintype "passive"))
      (node (ref "SV2") (pin "5") (pinfunction "5_5") (pintype "passive"))
    )
    (net (code "78") (name "/P38") (class "Default")
      (node (ref "JP2") (pin "6") (pinfunction "6_6") (pintype "passive"))
      (node (ref "SV2") (pin "6") (pinfunction "6_6") (pintype "passive"))
    )
    (net (code "79") (name "/P40") (class "Default")
      (node (ref "JP2") (pin "7") (pinfunction "7_7") (pintype "passive"))
      (node (ref "SV2") (pin "7") (pinfunction "7_7") (pintype "passive"))
    )
    (net (code "80") (name "/P41") (class "Default")
      (node (ref "JP2") (pin "8") (pinfunction "8_8") (pintype "passive"))
      (node (ref "SV2") (pin "8") (pinfunction "8_8") (pintype "passive"))
    )
    (net (code "81") (name "/P43") (class "Default")
      (node (ref "JP2") (pin "9") (pinfunction "9_9") (pintype "passive"))
      (node (ref "SV2") (pin "9") (pinfunction "9_9") (pintype "passive"))
    )
    (net (code "82") (name "/P44") (class "Default")
      (node (ref "JP2") (pin "10") (pinfunction "10_10") (pintype "passive"))
      (node (ref "SV2") (pin "10") (pinfunction "10_10") (pintype "passive"))
    )
    (net (code "83") (name "/P46") (class "Default")
      (node (ref "JP2") (pin "11") (pinfunction "11_11") (pintype "passive"))
      (node (ref "SV2") (pin "11") (pinfunction "11_11") (pintype "passive"))
    )
    (net (code "84") (name "/P47") (class "Default")
      (node (ref "JP2") (pin "12") (pinfunction "12_12") (pintype "passive"))
      (node (ref "SV2") (pin "12") (pinfunction "12_12") (pintype "passive"))
    )
    (net (code "85") (name "/P49") (class "Default")
      (node (ref "JP2") (pin "13") (pinfunction "13_13") (pintype "passive"))
      (node (ref "SV2") (pin "13") (pinfunction "13_13") (pintype "passive"))
    )
    (net (code "86") (name "/P50") (class "Default")
      (node (ref "JP2") (pin "14") (pinfunction "14_14") (pintype "passive"))
      (node (ref "SV2") (pin "14") (pinfunction "14_14") (pintype "passive"))
    )
    (net (code "87") (name "/P52") (class "Default")
      (node (ref "JP2") (pin "15") (pinfunction "15_15") (pintype "passive"))
      (node (ref "SV2") (pin "15") (pinfunction "15_15") (pintype "passive"))
    )
    (net (code "88") (name "/P53") (class "Default")
      (node (ref "JP2") (pin "16") (pinfunction "16_16") (pintype "passive"))
      (node (ref "SV2") (pin "16") (pinfunction "16_16") (pintype "passive"))
    )
    (net (code "89") (name "/P55") (class "Default")
      (node (ref "JP2") (pin "17") (pinfunction "17_17") (pintype "passive"))
      (node (ref "SV2") (pin "17") (pinfunction "17_17") (pintype "passive"))
    )
    (net (code "90") (name "/P56") (class "Default")
      (node (ref "JP2") (pin "18") (pinfunction "18_18") (pintype "passive"))
      (node (ref "SV2") (pin "18") (pinfunction "18_18") (pintype "passive"))
    )
    (net (code "91") (name "/P58") (class "Default")
      (node (ref "JP2") (pin "19") (pinfunction "19_19") (pintype "passive"))
      (node (ref "SV2") (pin "19") (pinfunction "19_19") (pintype "passive"))
    )
    (net (code "92") (name "/P59") (class "Default")
      (node (ref "JP2") (pin "20") (pinfunction "20_20") (pintype "passive"))
      (node (ref "SV2") (pin "20") (pinfunction "20_20") (pintype "passive"))
    )
    (net (code "93") (name "/P67") (class "Default")
      (node (ref "JP3") (pin "1") (pinfunction "1_1") (pintype "passive"))
      (node (ref "SV3") (pin "1") (pinfunction "1_1") (pintype "passive"))
    )
    (net (code "94") (name "/P68") (class "Default")
      (node (ref "JP3") (pin "2") (pinfunction "2_2") (pintype "passive"))
      (node (ref "SV3") (pin "2") (pinfunction "2_2") (pintype "passive"))
    )
    (net (code "95") (name "/P70") (class "Default")
      (node (ref "JP3") (pin "3") (pinfunction "3_3") (pintype "passive"))
      (node (ref "SV3") (pin "3") (pinfunction "3_3") (pintype "passive"))
    )
    (net (code "96") (name "/P71") (class "Default")
      (node (ref "JP3") (pin "4") (pinfunction "4_4") (pintype "passive"))
      (node (ref "SV3") (pin "4") (pinfunction "4_4") (pintype "passive"))
    )
    (net (code "97") (name "/P73") (class "Default")
      (node (ref "JP3") (pin "5") (pinfunction "5_5") (pintype "passive"))
      (node (ref "SV3") (pin "5") (pinfunction "5_5") (pintype "passive"))
    )
    (net (code "98") (name "/P74") (class "Default")
      (node (ref "JP3") (pin "6") (pinfunction "6_6") (pintype "passive"))
      (node (ref "SV3") (pin "6") (pinfunction "6_6") (pintype "passive"))
    )
    (net (code "99") (name "/P76") (class "Default")
      (node (ref "JP3") (pin "7") (pinfunction "7_7") (pintype "passive"))
      (node (ref "SV3") (pin "7") (pinfunction "7_7") (pintype "passive"))
    )
    (net (code "100") (name "/P77") (class "Default")
      (node (ref "JP3") (pin "8") (pinfunction "8_8") (pintype "passive"))
      (node (ref "SV3") (pin "8") (pinfunction "8_8") (pintype "passive"))
    )
    (net (code "101") (name "/P79") (class "Default")
      (node (ref "JP3") (pin "9") (pinfunction "9_9") (pintype "passive"))
      (node (ref "SV3") (pin "9") (pinfunction "9_9") (pintype "passive"))
    )
    (net (code "102") (name "/P80") (class "Default")
      (node (ref "JP3") (pin "10") (pinfunction "10_10") (pintype "passive"))
      (node (ref "SV3") (pin "10") (pinfunction "10_10") (pintype "passive"))
    )
    (net (code "103") (name "/P82") (class "Default")
      (node (ref "JP3") (pin "11") (pinfunction "11_11") (pintype "passive"))
      (node (ref "SV3") (pin "11") (pinfunction "11_11") (pintype "passive"))
    )
    (net (code "104") (name "/P83") (class "Default")
      (node (ref "JP3") (pin "12") (pinfunction "12_12") (pintype "passive"))
      (node (ref "SV3") (pin "12") (pinfunction "12_12") (pintype "passive"))
    )
    (net (code "105") (name "/P85") (class "Default")
      (node (ref "JP3") (pin "13") (pinfunction "13_13") (pintype "passive"))
      (node (ref "SV3") (pin "13") (pinfunction "13_13") (pintype "passive"))
    )
    (net (code "106") (name "/P86") (class "Default")
      (node (ref "JP3") (pin "14") (pinfunction "14_14") (pintype "passive"))
      (node (ref "SV3") (pin "14") (pinfunction "14_14") (pintype "passive"))
    )
    (net (code "107") (name "/P88") (class "Default")
      (node (ref "JP3") (pin "15") (pinfunction "15_15") (pintype "passive"))
      (node (ref "SV3") (pin "15") (pinfunction "15_15") (pintype "passive"))
    )
    (net (code "108") (name "/P89") (class "Default")
      (node (ref "JP3") (pin "16") (pinfunction "16_16") (pintype "passive"))
      (node (ref "SV3") (pin "16") (pinfunction "16_16") (pintype "passive"))
    )
    (net (code "109") (name "/RD+") (class "Default")
      (node (ref "R13") (pin "1") (pinfunction "1_1") (pintype "passive"))
      (node (ref "U$3") (pin "4") (pinfunction "D+_4") (pintype "bidirectional"))
    )
    (net (code "110") (name "/RD-") (class "Default")
      (node (ref "R14") (pin "2") (pinfunction "2_2") (pintype "passive"))
      (node (ref "U$3") (pin "3") (pinfunction "D-_3") (pintype "bidirectional"))
    )
    (net (code "111") (name "/RESET") (class "Default")
      (node (ref "D1") (pin "A") (pinfunction "A_A") (pintype "passive"))
      (node (ref "ICSP") (pin "5") (pinfunction "5_5") (pintype "passive"))
      (node (ref "R16") (pin "2") (pinfunction "2_2") (pintype "passive"))
      (node (ref "S6") (pin "P$2") (pinfunction "2_P$2") (pintype "passive"))
      (node (ref "U$3") (pin "13") (pinfunction "~{RESET}_13") (pintype "bidirectional"))
    )
    (net (code "112") (name "/SCK") (class "Default")
      (node (ref "ICSP") (pin "3") (pinfunction "3_3") (pintype "passive"))
      (node (ref "U$3") (pin "9") (pinfunction "PB1(SCK)_9") (pintype "bidirectional"))
    )
    (net (code "113") (name "/UGND") (class "Default")
      (node (ref "C12") (pin "2") (pinfunction "2_2") (pintype "passive"))
      (node (ref "C15") (pin "2") (pinfunction "2_2") (pintype "passive"))
      (node (ref "L1") (pin "1") (pinfunction "1_1") (pintype "passive"))
      (node (ref "U$1") (pin "GND") (pinfunction "GND_GND") (pintype "bidirectional"))
      (node (ref "U$1") (pin "MTN1") (pinfunction "MTN2_MTN1") (pintype "bidirectional"))
      (node (ref "U$1") (pin "MTN2") (pinfunction "MTN3_MTN2") (pintype "bidirectional"))
      (node (ref "U$1") (pin "MTN3") (pinfunction "MTN1_MTN3") (pintype "bidirectional"))
      (node (ref "U$1") (pin "MTN4") (pinfunction "MTN4_MTN4") (pintype "bidirectional"))
      (node (ref "U$3") (pin "5") (pinfunction "UGND_5") (pintype "bidirectional"))
    )
    (net (code "114") (name "/WC1") (class "Default")
      (node (ref "JP9") (pin "1") (pinfunction "1_1") (pintype "passive"))
      (node (ref "JP9") (pin "13") (pinfunction "13_13") (pintype "passive"))
      (node (ref "JP9") (pin "8") (pinfunction "8_8") (pintype "passive"))
      (node (ref "WIRELESSCON") (pin "P$6") (pinfunction "P$6_P$6") (pintype "bidirectional"))
    )
    (net (code "115") (name "/WC2") (class "Default")
      (node (ref "JP9") (pin "16") (pinfunction "16_16") (pintype "passive"))
      (node (ref "JP9") (pin "7") (pinfunction "7_7") (pintype "passive"))
      (node (ref "WIRELESSCON") (pin "P$5") (pinfunction "P$5_P$5") (pintype "bidirectional"))
    )
    (net (code "116") (name "/WC3") (class "Default")
      (node (ref "JP9") (pin "15") (pinfunction "15_15") (pintype "passive"))
      (node (ref "JP9") (pin "9") (pinfunction "9_9") (pintype "passive"))
      (node (ref "WIRELESSCON") (pin "P$4") (pinfunction "P$4_P$4") (pintype "bidirectional"))
    )
    (net (code "117") (name "/WC4") (class "Default")
      (node (ref "JP9") (pin "10") (pinfunction "10_10") (pintype "passive"))
      (node (ref "JP9") (pin "18") (pinfunction "18_18") (pintype "passive"))
      (node (ref "WIRELESSCON") (pin "P$3") (pinfunction "P$3_P$3") (pintype "bidirectional"))
    )
    (net (code "118") (name "/WC5") (class "Default")
      (node (ref "JP9") (pin "11") (pinfunction "11_11") (pintype "passive"))
      (node (ref "JP9") (pin "17") (pinfunction "17_17") (pintype "passive"))
      (node (ref "WIRELESSCON") (pin "P$2") (pinfunction "P$2_P$2") (pintype "bidirectional"))
    )
    (net (code "119") (name "/WC6") (class "Default")
      (node (ref "JP9") (pin "12") (pinfunction "12_12") (pintype "passive"))
      (node (ref "JP9") (pin "20") (pinfunction "20_20") (pintype "passive"))
      (node (ref "WIRELESSCON") (pin "P$1") (pinfunction "P$1_P$1") (pintype "bidirectional"))
    )
    (net (code "120") (name "AGND") (class "Default")
      (node (ref "C10") (pin "2") (pinfunction "2_2") (pintype "passive"))
      (node (ref "C24") (pin "2") (pinfunction "2_2") (pintype "passive"))
      (node (ref "L3") (pin "1") (pinfunction "1_1") (pintype "passive"))
      (node (ref "U$3") (pin "43") (pinfunction "GND_43") (pintype "bidirectional"))
    )
    (net (code "121") (name "GND") (class "Default")
      (node (ref "C1") (pin "-") (pinfunction "-_-") (pintype "passive"))
      (node (ref "C11") (pin "2") (pinfunction "2_2") (pintype "passive"))
      (node (ref "C13") (pin "2") (pinfunction "2_2") (pintype "passive"))
      (node (ref "C14") (pin "1") (pinfunction "1_1") (pintype "passive"))
      (node (ref "C16") (pin "2") (pinfunction "2_2") (pintype "passive"))
      (node (ref "C17") (pin "2") (pinfunction "2_2") (pintype "passive"))
      (node (ref "C18") (pin "1") (pinfunction "1_1") (pintype "passive"))
      (node (ref "C2") (pin "-") (pinfunction "-_-") (pintype "passive"))
      (node (ref "C2*") (pin "2") (pinfunction "2_2") (pintype "passive"))
      (node (ref "C22") (pin "-") (pinfunction "-_-") (pintype "passive"))
      (node (ref "C23") (pin "-") (pinfunction "-_-") (pintype "passive"))
      (node (ref "C23*") (pin "2") (pinfunction "2_2") (pintype "passive"))
      (node (ref "C25") (pin "-") (pinfunction "-_-") (pintype "passive"))
      (node (ref "C26") (pin "2") (pinfunction "2_2") (pintype "passive"))
      (node (ref "C27") (pin "2") (pinfunction "2_2") (pintype "passive"))
      (node (ref "C28") (pin "2") (pinfunction "2_2") (pintype "passive"))
      (node (ref "C29") (pin "2") (pinfunction "2_2") (pintype "passive"))
      (node (ref "C3") (pin "-") (pinfunction "-_-") (pintype "passive"))
      (node (ref "C3*") (pin "2") (pinfunction "2_2") (pintype "passive"))
      (node (ref "C4") (pin "-") (pinfunction "-_-") (pintype "passive"))
      (node (ref "C4*") (pin "2") (pinfunction "2_2") (pintype "passive"))
      (node (ref "C5") (pin "2") (pinfunction "2_2") (pintype "passive"))
      (node (ref "C6") (pin "2") (pinfunction "2_2") (pintype "passive"))
      (node (ref "C7") (pin "2") (pinfunction "2_2") (pintype "passive"))
      (node (ref "C8") (pin "2") (pinfunction "2_2") (pintype "passive"))
      (node (ref "DC_IN") (pin "1") (pinfunction "1_1") (pintype "passive"))
      (node (ref "DISP2") (pin "P$1") (pinfunction "P$1_P$1") (pintype "bidirectional"))
      (node (ref "IC1") (pin "1") (pinfunction "ADJ_1") (pintype "input"))
      (node (ref "IC2") (pin "1") (pinfunction "ADJ_1") (pintype "input"))
      (node (ref "ICSP") (pin "6") (pinfunction "6_6") (pintype "passive"))
      (node (ref "JP5") (pin "3") (pinfunction "3_3") (pintype "passive"))
      (node (ref "JP5") (pin "4") (pinfunction "4_4") (pintype "passive"))
      (node (ref "JP9") (pin "14") (pinfunction "14_14") (pintype "passive"))
      (node (ref "JP9") (pin "5") (pinfunction "5_5") (pintype "passive"))
      (node (ref "L1") (pin "2") (pinfunction "2_2") (pintype "passive"))
      (node (ref "L3") (pin "2") (pinfunction "2_2") (pintype "passive"))
      (node (ref "LED1") (pin "C") (pinfunction "C_C") (pintype "passive"))
      (node (ref "LED2") (pin "C") (pinfunction "C_C") (pintype "passive"))
      (node (ref "LED3") (pin "C") (pinfunction "C_C") (pintype "passive"))
      (node (ref "LED4") (pin "C") (pinfunction "C_C") (pintype "passive"))
      (node (ref "LED5") (pin "C") (pinfunction "C_C") (pintype "passive"))
      (node (ref "LED6") (pin "C") (pinfunction "C_C") (pintype "passive"))
      (node (ref "LED7") (pin "C") (pinfunction "C_C") (pintype "passive"))
      (node (ref "LED8") (pin "C") (pinfunction "C_C") (pintype "passive"))
      (node (ref "LED9") (pin "C") (pinfunction "C_C") (pintype "passive"))
      (node (ref "PROTOBOARD") (pin "P$2") (pinfunction "P$2_P$2") (pintype "bidirectional"))
      (node (ref "Q1") (pin "2") (pinfunction "S_2") (pintype "passive"))
      (node (ref "R10") (pin "1") (pinfunction "1_1") (pintype "passive"))
      (node (ref "R11") (pin "1") (pinfunction "1_1") (pintype "passive"))
      (node (ref "R12") (pin "1") (pinfunction "1_1") (pintype "passive"))
      (node (ref "R15") (pin "2") (pinfunction "2_2") (pintype "passive"))
      (node (ref "R17") (pin "A") (pinfunction "A_A") (pintype "passive"))
      (node (ref "R18") (pin "A") (pinfunction "A_A") (pintype "passive"))
      (node (ref "R19") (pin "2") (pinfunction "2_2") (pintype "passive"))
      (node (ref "R21") (pin "1") (pinfunction "1_1") (pintype "passive"))
      (node (ref "R22") (pin "2") (pinfunction "2_2") (pintype "passive"))
      (node (ref "R23") (pin "2") (pinfunction "2_2") (pintype "passive"))
      (node (ref "R24") (pin "2") (pinfunction "2_2") (pintype "passive"))
      (node (ref "R25") (pin "2") (pinfunction "2_2") (pintype "passive"))
      (node (ref "R31") (pin "2") (pinfunction "2_2") (pintype "passive"))
      (node (ref "R9") (pin "1") (pinfunction "1_1") (pintype "passive"))
      (node (ref "S6") (pin "P$1") (pinfunction "1_P$1") (pintype "passive"))
      (node (ref "T2") (pin "3") (pinfunction "G_3") (pintype "passive"))
      (node (ref "U$3") (pin "15") (pinfunction "GND_15") (pintype "bidirectional"))
      (node (ref "U$3") (pin "23") (pinfunction "GND_23") (pintype "bidirectional"))
      (node (ref "U$3") (pin "35") (pinfunction "GND_35") (pintype "bidirectional"))
      (node (ref "U$4") (pin "P$2") (pinfunction "P$2_P$2") (pintype "bidirectional"))
      (node (ref "U2") (pin "7") (pinfunction "GND_7") (pintype "bidirectional"))
    )
    (net (code "122") (name "Net-(C15-Pad1)") (class "Default")
      (node (ref "C15") (pin "1") (pinfunction "1_1") (pintype "passive"))
      (node (ref "PTC") (pin "1") (pinfunction "1_1") (pintype "passive"))
      (node (ref "U$1") (pin "VBUS") (pinfunction "VBUS_VBUS") (pintype "bidirectional"))
    )
    (net (code "123") (name "Net-(C26-Pad1)") (class "Default")
      (node (ref "C26") (pin "1") (pinfunction "1_1") (pintype "passive"))
      (node (ref "JP8") (pin "16") (pinfunction "16_16") (pintype "passive"))
      (node (ref "R17") (pin "S") (pinfunction "S_S") (pintype "passive"))
    )
    (net (code "124") (name "Net-(C27-Pad1)") (class "Default")
      (node (ref "C27") (pin "1") (pinfunction "1_1") (pintype "passive"))
      (node (ref "JP8") (pin "6") (pinfunction "6_6") (pintype "passive"))
      (node (ref "R18") (pin "S") (pinfunction "S_S") (pintype "passive"))
    )
    (net (code "125") (name "Net-(DC_IN-Pad2)") (class "Default")
      (node (ref "DC_IN") (pin "2") (pinfunction "2_2") (pintype "passive"))
      (node (ref "U$2") (pin "PA") (pinfunction "PA_PA") (pintype "passive"))
      (node (ref "U$2") (pin "PCOM") (pinfunction "PCOM_PCOM") (pintype "passive"))
    )
    (net (code "126") (name "Net-(JP4-PadP$1)") (class "Default")
      (node (ref "JP4") (pin "P$1") (pinfunction "P$1_P$1") (pintype "bidirectional"))
      (node (ref "R15") (pin "1") (pinfunction "1_1") (pintype "passive"))
    )
    (net (code "127") (name "Net-(JP8-Pad1)") (class "Default")
      (node (ref "JP8") (pin "1") (pinfunction "1_1") (pintype "passive"))
      (node (ref "R8") (pin "2") (pinfunction "2_2") (pintype "passive"))
    )
    (net (code "128") (name "Net-(JP8-Pad3)") (class "Default")
      (node (ref "JP8") (pin "3") (pinfunction "3_3") (pintype "passive"))
      (node (ref "R7") (pin "2") (pinfunction "2_2") (pintype "passive"))
    )
    (net (code "129") (name "Net-(JP8-Pad5)") (class "Default")
      (node (ref "JP8") (pin "5") (pinfunction "5_5") (pintype "passive"))
      (node (ref "R6") (pin "2") (pinfunction "2_2") (pintype "passive"))
    )
    (net (code "130") (name "Net-(JP8-Pad7)") (class "Default")
      (node (ref "JP8") (pin "7") (pinfunction "7_7") (pintype "passive"))
      (node (ref "R5") (pin "2") (pinfunction "2_2") (pintype "passive"))
    )
    (net (code "131") (name "Net-(JP8-Pad8)") (class "Default")
      (node (ref "JP8") (pin "8") (pinfunction "8_8") (pintype "passive"))
      (node (ref "R11") (pin "2") (pinfunction "2_2") (pintype "passive"))
      (node (ref "S4") (pin "1") (pinfunction "1_1") (pintype "passive"))
    )
    (net (code "132") (name "Net-(JP8-Pad9)") (class "Default")
      (node (ref "JP8") (pin "9") (pinfunction "9_9") (pintype "passive"))
      (node (ref "R4") (pin "2") (pinfunction "2_2") (pintype "passive"))
    )
    (net (code "133") (name "Net-(JP8-Pad10)") (class "Default")
      (node (ref "JP8") (pin "10") (pinfunction "10_10") (pintype "passive"))
      (node (ref "R10") (pin "2") (pinfunction "2_2") (pintype "passive"))
      (node (ref "S3") (pin "1") (pinfunction "1_1") (pintype "passive"))
    )
    (net (code "134") (name "Net-(JP8-Pad11)") (class "Default")
      (node (ref "JP8") (pin "11") (pinfunction "11_11") (pintype "passive"))
      (node (ref "R3") (pin "2") (pinfunction "2_2") (pintype "passive"))
    )
    (net (code "135") (name "Net-(JP8-Pad12)") (class "Default")
      (node (ref "JP8") (pin "12") (pinfunction "12_12") (pintype "passive"))
      (node (ref "R12") (pin "2") (pinfunction "2_2") (pintype "passive"))
      (node (ref "S5") (pin "1") (pinfunction "1_1") (pintype "passive"))
    )
    (net (code "136") (name "Net-(JP8-Pad13)") (class "Default")
      (node (ref "JP8") (pin "13") (pinfunction "13_13") (pintype "passive"))
      (node (ref "R2") (pin "2") (pinfunction "2_2") (pintype "passive"))
    )
    (net (code "137") (name "Net-(JP8-Pad14)") (class "Default")
      (node (ref "JP8") (pin "14") (pinfunction "14_14") (pintype "passive"))
      (node (ref "R9") (pin "2") (pinfunction "2_2") (pintype "passive"))
      (node (ref "S2") (pin "1") (pinfunction "1_1") (pintype "passive"))
    )
    (net (code "138") (name "Net-(JP8-Pad15)") (class "Default")
      (node (ref "JP8") (pin "15") (pinfunction "15_15") (pintype "passive"))
      (node (ref "R1") (pin "2") (pinfunction "2_2") (pintype "passive"))
    )
    (net (code "139") (name "Net-(LED1-PadA)") (class "Default")
      (node (ref "LED1") (pin "A") (pinfunction "A_A") (pintype "passive"))
      (node (ref "R1") (pin "1") (pinfunction "1_1") (pintype "passive"))
    )
    (net (code "140") (name "Net-(LED2-PadA)") (class "Default")
      (node (ref "LED2") (pin "A") (pinfunction "A_A") (pintype "passive"))
      (node (ref "R2") (pin "1") (pinfunction "1_1") (pintype "passive"))
    )
    (net (code "141") (name "Net-(LED3-PadA)") (class "Default")
      (node (ref "LED3") (pin "A") (pinfunction "A_A") (pintype "passive"))
      (node (ref "R3") (pin "1") (pinfunction "1_1") (pintype "passive"))
    )
    (net (code "142") (name "Net-(LED4-PadA)") (class "Default")
      (node (ref "LED4") (pin "A") (pinfunction "A_A") (pintype "passive"))
      (node (ref "R4") (pin "1") (pinfunction "1_1") (pintype "passive"))
    )
    (net (code "143") (name "Net-(LED5-PadA)") (class "Default")
      (node (ref "LED5") (pin "A") (pinfunction "A_A") (pintype "passive"))
      (node (ref "R5") (pin "1") (pinfunction "1_1") (pintype "passive"))
    )
    (net (code "144") (name "Net-(LED6-PadA)") (class "Default")
      (node (ref "LED6") (pin "A") (pinfunction "A_A") (pintype "passive"))
      (node (ref "R6") (pin "1") (pinfunction "1_1") (pintype "passive"))
    )
    (net (code "145") (name "Net-(LED7-PadA)") (class "Default")
      (node (ref "LED7") (pin "A") (pinfunction "A_A") (pintype "passive"))
      (node (ref "R7") (pin "1") (pinfunction "1_1") (pintype "passive"))
    )
    (net (code "146") (name "Net-(LED8-PadA)") (class "Default")
      (node (ref "LED8") (pin "A") (pinfunction "A_A") (pintype "passive"))
      (node (ref "R8") (pin "1") (pinfunction "1_1") (pintype "passive"))
    )
    (net (code "147") (name "Net-(LED9-PadA)") (class "Default")
      (node (ref "LED9") (pin "A") (pinfunction "A_A") (pintype "passive"))
      (node (ref "R20") (pin "1") (pinfunction "1_1") (pintype "passive"))
    )
    (net (code "148") (name "Net-(Q1-D)") (class "Default")
      (node (ref "D2") (pin "A") (pinfunction "A_A") (pintype "passive"))
      (node (ref "Q1") (pin "3") (pinfunction "D_3") (pintype "passive"))
      (node (ref "SPK1") (pin "-") (pinfunction "+_-") (pintype "passive"))
    )
    (net (code "149") (name "Net-(Q1-G)") (class "Default")
      (node (ref "Q1") (pin "1") (pinfunction "G_1") (pintype "passive"))
      (node (ref "R19") (pin "1") (pinfunction "1_1") (pintype "passive"))
      (node (ref "R26") (pin "2") (pinfunction "2_2") (pintype "passive"))
    )
    (net (code "150") (name "Net-(S7-1)") (class "Default")
      (node (ref "R24") (pin "1") (pinfunction "1_1") (pintype "passive"))
      (node (ref "R29") (pin "2") (pinfunction "2_2") (pintype "passive"))
      (node (ref "S7") (pin "P$1") (pinfunction "1_P$1") (pintype "passive"))
    )
    (net (code "151") (name "Net-(S8-1)") (class "Default")
      (node (ref "R25") (pin "1") (pinfunction "1_1") (pintype "passive"))
      (node (ref "R30") (pin "2") (pinfunction "2_2") (pintype "passive"))
      (node (ref "S8") (pin "P$1") (pinfunction "1_P$1") (pintype "passive"))
    )
    (net (code "152") (name "Net-(S9-1)") (class "Default")
      (node (ref "R22") (pin "1") (pinfunction "1_1") (pintype "passive"))
      (node (ref "R28") (pin "2") (pinfunction "2_2") (pintype "passive"))
      (node (ref "S9") (pin "P$1") (pinfunction "1_P$1") (pintype "passive"))
    )
    (net (code "153") (name "Net-(S10-1)") (class "Default")
      (node (ref "R23") (pin "1") (pinfunction "1_1") (pintype "passive"))
      (node (ref "R27") (pin "2") (pinfunction "2_2") (pintype "passive"))
      (node (ref "S10") (pin "P$1") (pinfunction "1_P$1") (pintype "passive"))
    )
    (net (code "154") (name "Net-(U$3-UCAP)") (class "Default")
      (node (ref "C12") (pin "1") (pinfunction "1_1") (pintype "passive"))
      (node (ref "U$3") (pin "6") (pinfunction "UCAP_6") (pintype "bidirectional"))
    )
    (net (code "155") (name "Net-(U$3-XTAL1)") (class "Default")
      (node (ref "C13") (pin "1") (pinfunction "1_1") (pintype "passive"))
      (node (ref "Q2") (pin "2") (pinfunction "2_2") (pintype "passive"))
      (node (ref "U$3") (pin "17") (pinfunction "XTAL1_17") (pintype "bidirectional"))
    )
    (net (code "156") (name "Net-(U$3-XTAL2)") (class "Default")
      (node (ref "C14") (pin "2") (pinfunction "2_2") (pintype "passive"))
      (node (ref "Q2") (pin "1") (pinfunction "1_1") (pintype "passive"))
      (node (ref "U$3") (pin "16") (pinfunction "XTAL2_16") (pintype "bidirectional"))
    )
    (net (code "157") (name "V+") (class "Default")
      (node (ref "T2") (pin "1") (pinfunction "D_1") (pintype "passive"))
      (node (ref "U$2") (pin "PB") (pinfunction "PB_PB") (pintype "passive"))
    )
    (net (code "158") (name "VBUS") (class "Default")
      (node (ref "C17") (pin "1") (pinfunction "1_1") (pintype "passive"))
      (node (ref "C18") (pin "2") (pinfunction "2_2") (pintype "passive"))
      (node (ref "PTC") (pin "2") (pinfunction "2_2") (pintype "passive"))
      (node (ref "T1") (pin "1") (pinfunction "D_1") (pintype "passive"))
      (node (ref "U$3") (pin "7") (pinfunction "VBUS_7") (pintype "bidirectional"))
    )
    (net (code "159") (name "VCC") (class "Default")
      (node (ref "C1") (pin "+") (pinfunction "+_+") (pintype "passive"))
      (node (ref "C2") (pin "+") (pinfunction "+_+") (pintype "passive"))
      (node (ref "C2*") (pin "1") (pinfunction "1_1") (pintype "passive"))
      (node (ref "C6") (pin "1") (pinfunction "1_1") (pintype "passive"))
      (node (ref "C7") (pin "1") (pinfunction "1_1") (pintype "passive"))
      (node (ref "C8") (pin "1") (pinfunction "1_1") (pintype "passive"))
      (node (ref "IC1") (pin "3") (pinfunction "IN_3") (pintype "input"))
      (node (ref "R21") (pin "2") (pinfunction "2_2") (pintype "passive"))
      (node (ref "T1") (pin "3") (pinfunction "G_3") (pintype "passive"))
      (node (ref "T2") (pin "2") (pinfunction "S_2") (pintype "passive"))
    )
    (net (code "160") (name "unconnected-(S2-Pad2)") (class "Default")
      (node (ref "S2") (pin "2") (pinfunction "2_2") (pintype "passive"))
    )
    (net (code "161") (name "unconnected-(S2-Pad4)") (class "Default")
      (node (ref "S2") (pin "4") (pinfunction "4_4") (pintype "passive"))
    )
    (net (code "162") (name "unconnected-(S3-Pad2)") (class "Default")
      (node (ref "S3") (pin "2") (pinfunction "2_2") (pintype "passive"))
    )
    (net (code "163") (name "unconnected-(S3-Pad4)") (class "Default")
      (node (ref "S3") (pin "4") (pinfunction "4_4") (pintype "passive"))
    )
    (net (code "164") (name "unconnected-(S4-Pad2)") (class "Default")
      (node (ref "S4") (pin "2") (pinfunction "2_2") (pintype "passive"))
    )
    (net (code "165") (name "unconnected-(S4-Pad4)") (class "Default")
      (node (ref "S4") (pin "4") (pinfunction "4_4") (pintype "passive"))
    )
    (net (code "166") (name "unconnected-(S5-Pad2)") (class "Default")
      (node (ref "S5") (pin "2") (pinfunction "2_2") (pintype "passive"))
    )
    (net (code "167") (name "unconnected-(S5-Pad4)") (class "Default")
      (node (ref "S5") (pin "4") (pinfunction "4_4") (pintype "passive"))
    )
    (net (code "168") (name "unconnected-(U$4-PadP$6)") (class "Default")
      (node (ref "U$4") (pin "P$6") (pinfunction "P$6_P$6") (pintype "bidirectional"))
    )
  )
)
